# halloween-eyes.net
KiCad netlist of a schematic drawn in EAGLE
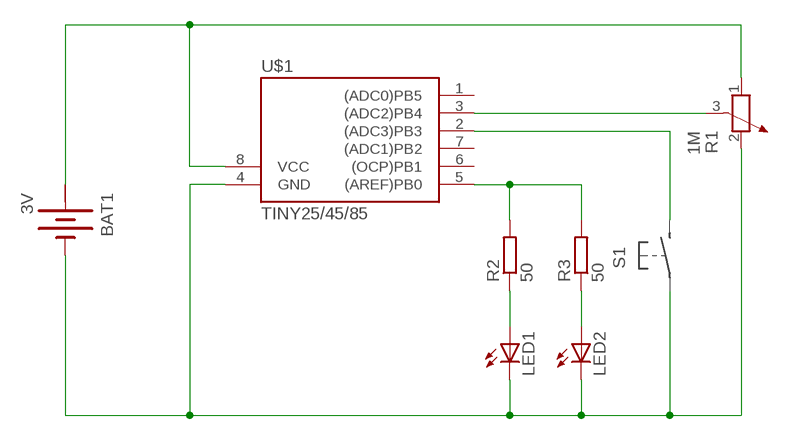
[diagram p0: schematic, sheet 1]

(export (version "E")
  (design (tool "Eeschema 10.0.6"))
  (components
    (comp (ref "BAT1")
      (value "3V")
      (footprint "eagle-import:BATTERY")
      (libsource (lib "eagle-import") (part "BATTERY"))
    )
    (comp (ref "LED1")
      (value "LED5MM")
      (footprint "eagle-import:LED5MM")
      (libsource (lib "eagle-import") (part "LED5MM"))
    )
    (comp (ref "LED2")
      (value "LED5MM")
      (footprint "eagle-import:LED5MM")
      (libsource (lib "eagle-import") (part "LED5MM"))
    )
    (comp (ref "R1")
      (value "1M")
      (footprint "eagle-import:PT-10")
      (libsource (lib "eagle-import") (part "POTENTIOMETER_PT-10"))
    )
    (comp (ref "R2")
      (value "50")
      (footprint "eagle-import:0207_10")
      (libsource (lib "eagle-import") (part "R-EU_0207/10"))
    )
    (comp (ref "R3")
      (value "50")
      (footprint "eagle-import:0207_10")
      (libsource (lib "eagle-import") (part "R-EU_0207/10"))
    )
    (comp (ref "U$1")
      (value "TINY25/45/85")
      (footprint "eagle-import:DIL08")
      (libsource (lib "eagle-import") (part "TINY25/45/85"))
    )
  )
  (nets
    (net (code "1") (name "/+") (class "Default")
      (node (ref "BAT1") (pin "+@1") (pinfunction "+_+@1") (pintype "power_in"))
    )
    (net (code "2") (name "Net-(LED1-C)") (class "Default")
      (node (ref "BAT1") (pin "-") (pinfunction "-_-") (pintype "power_in"))
      (node (ref "LED1") (pin "K") (pinfunction "C_K") (pintype "passive"))
      (node (ref "LED2") (pin "K") (pinfunction "C_K") (pintype "passive"))
      (node (ref "R1") (pin "2") (pinfunction "2_2") (pintype "passive"))
      (node (ref "U$1") (pin "4") (pinfunction "GND_4") (pintype "power_in"))
    )
    (net (code "3") (name "Net-(LED1-PadA)") (class "Default")
      (node (ref "LED1") (pin "A") (pinfunction "A_A") (pintype "passive"))
      (node (ref "R2") (pin "1") (pinfunction "1_1") (pintype "passive"))
    )
    (net (code "4") (name "Net-(LED2-PadA)") (class "Default")
      (node (ref "LED2") (pin "A") (pinfunction "A_A") (pintype "passive"))
      (node (ref "R3") (pin "1") (pinfunction "1_1") (pintype "passive"))
    )
    (net (code "5") (name "Net-(U$1-(ADC2)PB4)") (class "Default")
      (node (ref "R1") (pin "3") (pinfunction "3_3") (pintype "passive"))
      (node (ref "U$1") (pin "3") (pinfunction "(ADC2)PB4_3") (pintype "bidirectional"))
    )
    (net (code "6") (name "Net-(U$1-(AREF)PB0)") (class "Default")
      (node (ref "R2") (pin "2") (pinfunction "2_2") (pintype "passive"))
      (node (ref "R3") (pin "2") (pinfunction "2_2") (pintype "passive"))
      (node (ref "U$1") (pin "5") (pinfunction "(AREF)PB0_5") (pintype "bidirectional"))
    )
    (net (code "7") (name "Net-(U$1-VCC)") (class "Default")
      (node (ref "BAT1") (pin "+") (pinfunction "+_+") (pintype "power_in"))
      (node (ref "R1") (pin "1") (pinfunction "1_1") (pintype "passive"))
      (node (ref "U$1") (pin "8") (pinfunction "VCC_8") (pintype "power_in"))
    )
    (net (code "8") (name "unconnected-(U$1-(ADC0)PB5-Pad1)") (class "Default")
      (node (ref "U$1") (pin "1") (pinfunction "(ADC0)PB5_1") (pintype "bidirectional"))
    )
    (net (code "9") (name "unconnected-(U$1-(ADC1)PB2-Pad7)") (class "Default")
      (node (ref "U$1") (pin "7") (pinfunction "(ADC1)PB2_7") (pintype "bidirectional"))
    )
    (net (code "10") (name "unconnected-(U$1-(ADC3)PB3-Pad2)") (class "Default")
      (node (ref "U$1") (pin "2") (pinfunction "(ADC3)PB3_2") (pintype "bidirectional"))
    )
    (net (code "11") (name "unconnected-(U$1-(OCP)PB1-Pad6)") (class "Default")
      (node (ref "U$1") (pin "6") (pinfunction "(OCP)PB1_6") (pintype "bidirectional"))
    )
  )
)
